# interface.net
KiCad netlist of a schematic drawn in Altium Designer
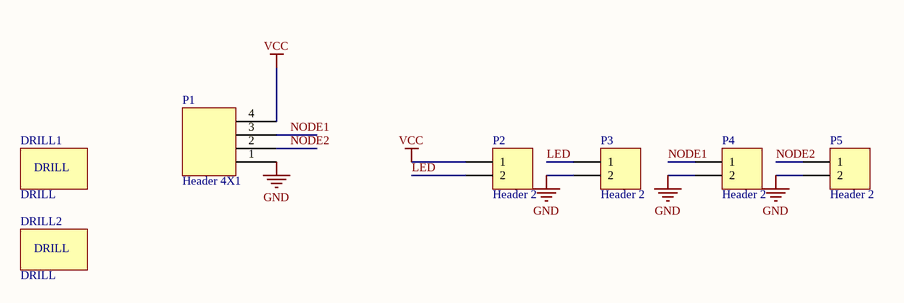
[diagram p0: interface.SchDoc]

(export (version "E")
  (design (tool "Eeschema 10.0.6"))
  (components
    (comp (ref "DRILL1") (value "DRILL") (footprint "DRILL_2MM") (libsource (lib "Inte") (part "DRILL")))
    (comp (ref "DRILL2") (value "DRILL") (footprint "DRILL_2MM") (libsource (lib "Inte") (part "DRILL")))
    (comp (ref "P1")
      (value "Header 4X1")
      (footprint "HDR4X1")
      (description "Header,4-Pin")
      (libsource (lib "Inte") (part "Header 4X1"))
    )
    (comp (ref "P2")
      (value "Header 2")
      (footprint "HDR1X2")
      (description "Header, 2-Pin")
      (fields (field (name "PUBLISHER") "Altium Limited"))
      (libsource (lib "Miscellaneous Connectors") (part "Header 2"))
    )
    (comp (ref "P3")
      (value "Header 2")
      (footprint "HDR1X2")
      (description "Header, 2-Pin")
      (fields (field (name "PUBLISHER") "Altium Limited"))
      (libsource (lib "Miscellaneous Connectors") (part "Header 2"))
    )
    (comp (ref "P4")
      (value "Header 2")
      (footprint "HDR1X2")
      (description "Header, 2-Pin")
      (fields (field (name "PUBLISHER") "Altium Limited"))
      (libsource (lib "Miscellaneous Connectors") (part "Header 2"))
    )
    (comp (ref "P5")
      (value "Header 2")
      (footprint "HDR1X2")
      (description "Header, 2-Pin")
      (fields (field (name "PUBLISHER") "Altium Limited"))
      (libsource (lib "Miscellaneous Connectors") (part "Header 2"))
    )
  )
  (nets
    (net (code "1") (name "/LED") (class "Default")
      (node (ref "P2") (pin "2") (pinfunction "2_2") (pintype "passive"))
      (node (ref "P3") (pin "1") (pinfunction "1_1") (pintype "passive"))
    )
    (net (code "2") (name "/NODE1") (class "Default")
      (node (ref "P1") (pin "3") (pinfunction "3_3") (pintype "passive"))
      (node (ref "P4") (pin "1") (pinfunction "1_1") (pintype "passive"))
    )
    (net (code "3") (name "/NODE2") (class "Default")
      (node (ref "P1") (pin "2") (pinfunction "2_2") (pintype "passive"))
      (node (ref "P5") (pin "1") (pinfunction "1_1") (pintype "passive"))
    )
    (net (code "4") (name "GND") (class "Default")
      (node (ref "P1") (pin "1") (pinfunction "1_1") (pintype "passive"))
      (node (ref "P3") (pin "2") (pinfunction "2_2") (pintype "passive"))
      (node (ref "P4") (pin "2") (pinfunction "2_2") (pintype "passive"))
      (node (ref "P5") (pin "2") (pinfunction "2_2") (pintype "passive"))
    )
    (net (code "5") (name "VCC") (class "Default")
      (node (ref "P1") (pin "4") (pinfunction "4_4") (pintype "passive"))
      (node (ref "P2") (pin "1") (pinfunction "1_1") (pintype "passive"))
    )
  )
)
